# f30bms-slaveboard-tester.net
KiCad netlist of a schematic drawn in Altium Designer
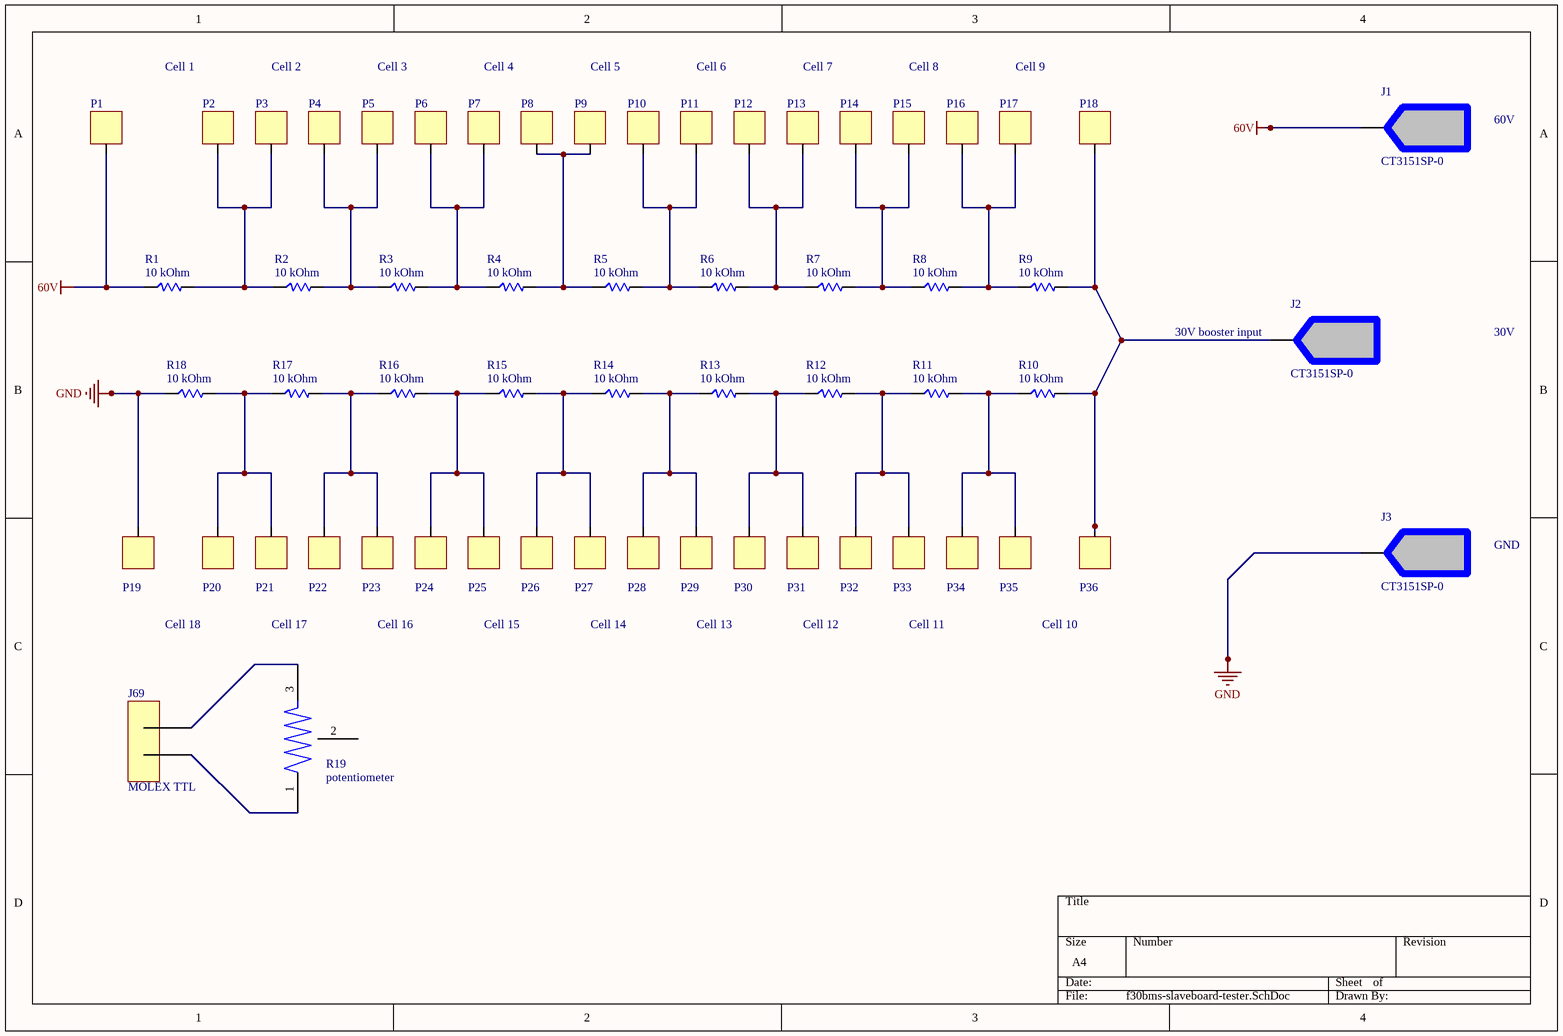
[diagram p0: f30bms-slaveboard-tester.SchDoc]

(export (version "E")
  (design (tool "Eeschema 10.0.6"))
  (components
    (comp (ref "J1")
      (value "CT3151SP-0")
      (footprint "CT3151SP-0")
      (description "Conn 4mm Safety Banana Jack F 1 POS Solder RA Thru-Hole 1 Port Bag")
      (fields (field (name "MANUFACTURER") "Cal Test Electronics"))
      (libsource (lib "connectors") (part "CT3151SP-0"))
    )
    (comp (ref "J2")
      (value "CT3151SP-0")
      (footprint "CT3151SP-0")
      (description "Conn 4mm Safety Banana Jack F 1 POS Solder RA Thru-Hole 1 Port Bag")
      (fields (field (name "MANUFACTURER") "Cal Test Electronics"))
      (libsource (lib "connectors") (part "CT3151SP-0"))
    )
    (comp (ref "J3")
      (value "CT3151SP-0")
      (footprint "CT3151SP-0")
      (description "Conn 4mm Safety Banana Jack F 1 POS Solder RA Thru-Hole 1 Port Bag")
      (fields (field (name "MANUFACTURER") "Cal Test Electronics"))
      (libsource (lib "connectors") (part "CT3151SP-0"))
    )
    (comp (ref "J69")
      (value "MOLEX TTL")
      (footprint "MOLEX TTL")
      (libsource (lib "connectors") (part "MOLEX TTL"))
    )
    (comp (ref "P1")
      (value "SLAVEBOARD CONTACT")
      (footprint "SLAVEBOARD CONTACT")
      (libsource (lib "connectors") (part "SLAVEBOARD CONTACT"))
    )
    (comp (ref "P2")
      (value "SLAVEBOARD CONTACT")
      (footprint "SLAVEBOARD CONTACT")
      (libsource (lib "connectors") (part "SLAVEBOARD CONTACT"))
    )
    (comp (ref "P3")
      (value "SLAVEBOARD CONTACT")
      (footprint "SLAVEBOARD CONTACT")
      (libsource (lib "connectors") (part "SLAVEBOARD CONTACT"))
    )
    (comp (ref "P4")
      (value "SLAVEBOARD CONTACT")
      (footprint "SLAVEBOARD CONTACT")
      (libsource (lib "connectors") (part "SLAVEBOARD CONTACT"))
    )
    (comp (ref "P5")
      (value "SLAVEBOARD CONTACT")
      (footprint "SLAVEBOARD CONTACT")
      (libsource (lib "connectors") (part "SLAVEBOARD CONTACT"))
    )
    (comp (ref "P6")
      (value "SLAVEBOARD CONTACT")
      (footprint "SLAVEBOARD CONTACT")
      (libsource (lib "connectors") (part "SLAVEBOARD CONTACT"))
    )
    (comp (ref "P7")
      (value "SLAVEBOARD CONTACT")
      (footprint "SLAVEBOARD CONTACT")
      (libsource (lib "connectors") (part "SLAVEBOARD CONTACT"))
    )
    (comp (ref "P8")
      (value "SLAVEBOARD CONTACT")
      (footprint "SLAVEBOARD CONTACT")
      (libsource (lib "connectors") (part "SLAVEBOARD CONTACT"))
    )
    (comp (ref "P9")
      (value "SLAVEBOARD CONTACT")
      (footprint "SLAVEBOARD CONTACT")
      (libsource (lib "connectors") (part "SLAVEBOARD CONTACT"))
    )
    (comp (ref "P10")
      (value "SLAVEBOARD CONTACT")
      (footprint "SLAVEBOARD CONTACT")
      (libsource (lib "connectors") (part "SLAVEBOARD CONTACT"))
    )
    (comp (ref "P11")
      (value "SLAVEBOARD CONTACT")
      (footprint "SLAVEBOARD CONTACT")
      (libsource (lib "connectors") (part "SLAVEBOARD CONTACT"))
    )
    (comp (ref "P12")
      (value "SLAVEBOARD CONTACT")
      (footprint "SLAVEBOARD CONTACT")
      (libsource (lib "connectors") (part "SLAVEBOARD CONTACT"))
    )
    (comp (ref "P13")
      (value "SLAVEBOARD CONTACT")
      (footprint "SLAVEBOARD CONTACT")
      (libsource (lib "connectors") (part "SLAVEBOARD CONTACT"))
    )
    (comp (ref "P14")
      (value "SLAVEBOARD CONTACT")
      (footprint "SLAVEBOARD CONTACT")
      (libsource (lib "connectors") (part "SLAVEBOARD CONTACT"))
    )
    (comp (ref "P15")
      (value "SLAVEBOARD CONTACT")
      (footprint "SLAVEBOARD CONTACT")
      (libsource (lib "connectors") (part "SLAVEBOARD CONTACT"))
    )
    (comp (ref "P16")
      (value "SLAVEBOARD CONTACT")
      (footprint "SLAVEBOARD CONTACT")
      (libsource (lib "connectors") (part "SLAVEBOARD CONTACT"))
    )
    (comp (ref "P17")
      (value "SLAVEBOARD CONTACT")
      (footprint "SLAVEBOARD CONTACT")
      (libsource (lib "connectors") (part "SLAVEBOARD CONTACT"))
    )
    (comp (ref "P18")
      (value "SLAVEBOARD CONTACT")
      (footprint "SLAVEBOARD CONTACT")
      (libsource (lib "connectors") (part "SLAVEBOARD CONTACT"))
    )
    (comp (ref "P19")
      (value "SLAVEBOARD CONTACT")
      (footprint "SLAVEBOARD CONTACT")
      (libsource (lib "") (part "SLAVEBOARD CONTACT_1"))
    )
    (comp (ref "P20")
      (value "SLAVEBOARD CONTACT")
      (footprint "SLAVEBOARD CONTACT")
      (libsource (lib "") (part "SLAVEBOARD CONTACT_1"))
    )
    (comp (ref "P21")
      (value "SLAVEBOARD CONTACT")
      (footprint "SLAVEBOARD CONTACT")
      (libsource (lib "") (part "SLAVEBOARD CONTACT_1"))
    )
    (comp (ref "P22")
      (value "SLAVEBOARD CONTACT")
      (footprint "SLAVEBOARD CONTACT")
      (libsource (lib "") (part "SLAVEBOARD CONTACT_1"))
    )
    (comp (ref "P23")
      (value "SLAVEBOARD CONTACT")
      (footprint "SLAVEBOARD CONTACT")
      (libsource (lib "") (part "SLAVEBOARD CONTACT_1"))
    )
    (comp (ref "P24")
      (value "SLAVEBOARD CONTACT")
      (footprint "SLAVEBOARD CONTACT")
      (libsource (lib "") (part "SLAVEBOARD CONTACT_1"))
    )
    (comp (ref "P25")
      (value "SLAVEBOARD CONTACT")
      (footprint "SLAVEBOARD CONTACT")
      (libsource (lib "") (part "SLAVEBOARD CONTACT_1"))
    )
    (comp (ref "P26")
      (value "SLAVEBOARD CONTACT")
      (footprint "SLAVEBOARD CONTACT")
      (libsource (lib "") (part "SLAVEBOARD CONTACT_1"))
    )
    (comp (ref "P27")
      (value "SLAVEBOARD CONTACT")
      (footprint "SLAVEBOARD CONTACT")
      (libsource (lib "") (part "SLAVEBOARD CONTACT_1"))
    )
    (comp (ref "P28")
      (value "SLAVEBOARD CONTACT")
      (footprint "SLAVEBOARD CONTACT")
      (libsource (lib "") (part "SLAVEBOARD CONTACT_1"))
    )
    (comp (ref "P29")
      (value "SLAVEBOARD CONTACT")
      (footprint "SLAVEBOARD CONTACT")
      (libsource (lib "") (part "SLAVEBOARD CONTACT_1"))
    )
    (comp (ref "P30")
      (value "SLAVEBOARD CONTACT")
      (footprint "SLAVEBOARD CONTACT")
      (libsource (lib "") (part "SLAVEBOARD CONTACT_1"))
    )
    (comp (ref "P31")
      (value "SLAVEBOARD CONTACT")
      (footprint "SLAVEBOARD CONTACT")
      (libsource (lib "") (part "SLAVEBOARD CONTACT_1"))
    )
    (comp (ref "P32")
      (value "SLAVEBOARD CONTACT")
      (footprint "SLAVEBOARD CONTACT")
      (libsource (lib "") (part "SLAVEBOARD CONTACT_1"))
    )
    (comp (ref "P33")
      (value "SLAVEBOARD CONTACT")
      (footprint "SLAVEBOARD CONTACT")
      (libsource (lib "") (part "SLAVEBOARD CONTACT_1"))
    )
    (comp (ref "P34")
      (value "SLAVEBOARD CONTACT")
      (footprint "SLAVEBOARD CONTACT")
      (libsource (lib "") (part "SLAVEBOARD CONTACT_1"))
    )
    (comp (ref "P35")
      (value "SLAVEBOARD CONTACT")
      (footprint "SLAVEBOARD CONTACT")
      (libsource (lib "") (part "SLAVEBOARD CONTACT_1"))
    )
    (comp (ref "P36")
      (value "SLAVEBOARD CONTACT")
      (footprint "SLAVEBOARD CONTACT")
      (libsource (lib "") (part "SLAVEBOARD CONTACT_1"))
    )
    (comp (ref "R1")
      (value "1622796-6")
      (footprint "CHP0805-FX-1002ELF - duplicate")
      (description "Res Thin Film 10K Ohm 0.1% 1/4W 15ppm/C Conformal AXL Thru-Hole Ammo Pack")
      (fields (field (name "MANUFACTURER") "TE Connectivity") (field (name "TOLERANCE") "0.1%"))
      (libsource (lib "resistors") (part "1622796-6"))
    )
    (comp (ref "R2")
      (value "1622796-6")
      (footprint "CHP0805-FX-1002ELF - duplicate")
      (description "Res Thin Film 10K Ohm 0.1% 1/4W 15ppm/C Conformal AXL Thru-Hole Ammo Pack")
      (fields (field (name "MANUFACTURER") "TE Connectivity") (field (name "TOLERANCE") "0.1%"))
      (libsource (lib "resistors") (part "1622796-6"))
    )
    (comp (ref "R3")
      (value "1622796-6")
      (footprint "CHP0805-FX-1002ELF - duplicate")
      (description "Res Thin Film 10K Ohm 0.1% 1/4W 15ppm/C Conformal AXL Thru-Hole Ammo Pack")
      (fields (field (name "MANUFACTURER") "TE Connectivity") (field (name "TOLERANCE") "0.1%"))
      (libsource (lib "resistors") (part "1622796-6"))
    )
    (comp (ref "R4")
      (value "1622796-6")
      (footprint "CHP0805-FX-1002ELF - duplicate")
      (description "Res Thin Film 10K Ohm 0.1% 1/4W 15ppm/C Conformal AXL Thru-Hole Ammo Pack")
      (fields (field (name "MANUFACTURER") "TE Connectivity") (field (name "TOLERANCE") "0.1%"))
      (libsource (lib "resistors") (part "1622796-6"))
    )
    (comp (ref "R5")
      (value "1622796-6")
      (footprint "CHP0805-FX-1002ELF - duplicate")
      (description "Res Thin Film 10K Ohm 0.1% 1/4W 15ppm/C Conformal AXL Thru-Hole Ammo Pack")
      (fields (field (name "MANUFACTURER") "TE Connectivity") (field (name "TOLERANCE") "0.1%"))
      (libsource (lib "resistors") (part "1622796-6"))
    )
    (comp (ref "R6")
      (value "1622796-6")
      (footprint "CHP0805-FX-1002ELF - duplicate")
      (description "Res Thin Film 10K Ohm 0.1% 1/4W 15ppm/C Conformal AXL Thru-Hole Ammo Pack")
      (fields (field (name "MANUFACTURER") "TE Connectivity") (field (name "TOLERANCE") "0.1%"))
      (libsource (lib "resistors") (part "1622796-6"))
    )
    (comp (ref "R7")
      (value "1622796-6")
      (footprint "CHP0805-FX-1002ELF - duplicate")
      (description "Res Thin Film 10K Ohm 0.1% 1/4W 15ppm/C Conformal AXL Thru-Hole Ammo Pack")
      (fields (field (name "MANUFACTURER") "TE Connectivity") (field (name "TOLERANCE") "0.1%"))
      (libsource (lib "resistors") (part "1622796-6"))
    )
    (comp (ref "R8")
      (value "1622796-6")
      (footprint "CHP0805-FX-1002ELF - duplicate")
      (description "Res Thin Film 10K Ohm 0.1% 1/4W 15ppm/C Conformal AXL Thru-Hole Ammo Pack")
      (fields (field (name "MANUFACTURER") "TE Connectivity") (field (name "TOLERANCE") "0.1%"))
      (libsource (lib "resistors") (part "1622796-6"))
    )
    (comp (ref "R9")
      (value "1622796-6")
      (footprint "CHP0805-FX-1002ELF - duplicate")
      (description "Res Thin Film 10K Ohm 0.1% 1/4W 15ppm/C Conformal AXL Thru-Hole Ammo Pack")
      (fields (field (name "MANUFACTURER") "TE Connectivity") (field (name "TOLERANCE") "0.1%"))
      (libsource (lib "resistors") (part "1622796-6"))
    )
    (comp (ref "R10")
      (value "1622796-6")
      (footprint "CHP0805-FX-1002ELF - duplicate")
      (description "Res Thin Film 10K Ohm 0.1% 1/4W 15ppm/C Conformal AXL Thru-Hole Ammo Pack")
      (fields (field (name "MANUFACTURER") "TE Connectivity") (field (name "TOLERANCE") "0.1%"))
      (libsource (lib "resistors") (part "1622796-6"))
    )
    (comp (ref "R11")
      (value "1622796-6")
      (footprint "CHP0805-FX-1002ELF - duplicate")
      (description "Res Thin Film 10K Ohm 0.1% 1/4W 15ppm/C Conformal AXL Thru-Hole Ammo Pack")
      (fields (field (name "MANUFACTURER") "TE Connectivity") (field (name "TOLERANCE") "0.1%"))
      (libsource (lib "resistors") (part "1622796-6"))
    )
    (comp (ref "R12")
      (value "1622796-6")
      (footprint "CHP0805-FX-1002ELF - duplicate")
      (description "Res Thin Film 10K Ohm 0.1% 1/4W 15ppm/C Conformal AXL Thru-Hole Ammo Pack")
      (fields (field (name "MANUFACTURER") "TE Connectivity") (field (name "TOLERANCE") "0.1%"))
      (libsource (lib "resistors") (part "1622796-6"))
    )
    (comp (ref "R13")
      (value "1622796-6")
      (footprint "CHP0805-FX-1002ELF - duplicate")
      (description "Res Thin Film 10K Ohm 0.1% 1/4W 15ppm/C Conformal AXL Thru-Hole Ammo Pack")
      (fields (field (name "MANUFACTURER") "TE Connectivity") (field (name "TOLERANCE") "0.1%"))
      (libsource (lib "resistors") (part "1622796-6"))
    )
    (comp (ref "R14")
      (value "1622796-6")
      (footprint "CHP0805-FX-1002ELF - duplicate")
      (description "Res Thin Film 10K Ohm 0.1% 1/4W 15ppm/C Conformal AXL Thru-Hole Ammo Pack")
      (fields (field (name "MANUFACTURER") "TE Connectivity") (field (name "TOLERANCE") "0.1%"))
      (libsource (lib "resistors") (part "1622796-6"))
    )
    (comp (ref "R15")
      (value "1622796-6")
      (footprint "CHP0805-FX-1002ELF - duplicate")
      (description "Res Thin Film 10K Ohm 0.1% 1/4W 15ppm/C Conformal AXL Thru-Hole Ammo Pack")
      (fields (field (name "MANUFACTURER") "TE Connectivity") (field (name "TOLERANCE") "0.1%"))
      (libsource (lib "resistors") (part "1622796-6"))
    )
    (comp (ref "R16")
      (value "1622796-6")
      (footprint "CHP0805-FX-1002ELF - duplicate")
      (description "Res Thin Film 10K Ohm 0.1% 1/4W 15ppm/C Conformal AXL Thru-Hole Ammo Pack")
      (fields (field (name "MANUFACTURER") "TE Connectivity") (field (name "TOLERANCE") "0.1%"))
      (libsource (lib "resistors") (part "1622796-6"))
    )
    (comp (ref "R17")
      (value "1622796-6")
      (footprint "CHP0805-FX-1002ELF - duplicate")
      (description "Res Thin Film 10K Ohm 0.1% 1/4W 15ppm/C Conformal AXL Thru-Hole Ammo Pack")
      (fields (field (name "MANUFACTURER") "TE Connectivity") (field (name "TOLERANCE") "0.1%"))
      (libsource (lib "resistors") (part "1622796-6"))
    )
    (comp (ref "R18")
      (value "1622796-6")
      (footprint "CHP0805-FX-1002ELF - duplicate")
      (description "Res Thin Film 10K Ohm 0.1% 1/4W 15ppm/C Conformal AXL Thru-Hole Ammo Pack")
      (fields (field (name "MANUFACTURER") "TE Connectivity") (field (name "TOLERANCE") "0.1%"))
      (libsource (lib "resistors") (part "1622796-6"))
    )
    (comp (ref "R19")
      (value "potentiometer")
      (footprint "3361P-1-103GLF_SOP3")
      (libsource (lib "resistors") (part "potentiometer"))
    )
  )
  (nets
    (net (code "1") (name "60V") (class "Default")
      (node (ref "J1") (pin "1") (pinfunction "1_1") (pintype "passive"))
      (node (ref "P1") (pin "1") (pinfunction "1_1") (pintype "passive"))
      (node (ref "R1") (pin "2") (pinfunction "2_2") (pintype "passive"))
    )
    (net (code "2") (name "GND") (class "Default")
      (node (ref "J3") (pin "1") (pinfunction "1_1") (pintype "passive"))
      (node (ref "P19") (pin "1") (pinfunction "1_1") (pintype "passive"))
      (node (ref "R18") (pin "2") (pinfunction "2_2") (pintype "passive"))
    )
    (net (code "3") (name "Net-(J2-Pad1)") (class "Default")
      (node (ref "J2") (pin "1") (pinfunction "1_1") (pintype "passive"))
      (node (ref "P18") (pin "1") (pinfunction "1_1") (pintype "passive"))
      (node (ref "P36") (pin "1") (pinfunction "1_1") (pintype "passive"))
      (node (ref "R10") (pin "1") (pinfunction "1_1") (pintype "passive"))
      (node (ref "R9") (pin "1") (pinfunction "1_1") (pintype "passive"))
    )
    (net (code "4") (name "Net-(J69-Pad1)") (class "Default")
      (node (ref "J69") (pin "1") (pinfunction "1_1") (pintype "passive"))
      (node (ref "R19") (pin "1") (pinfunction "1_1") (pintype "passive"))
    )
    (net (code "5") (name "Net-(J69-Pad2)") (class "Default")
      (node (ref "J69") (pin "2") (pinfunction "2_2") (pintype "passive"))
      (node (ref "R19") (pin "3") (pinfunction "3_3") (pintype "passive"))
    )
    (net (code "6") (name "Net-(P2-Pad1)") (class "Default")
      (node (ref "P2") (pin "1") (pinfunction "1_1") (pintype "passive"))
      (node (ref "P3") (pin "1") (pinfunction "1_1") (pintype "passive"))
      (node (ref "R1") (pin "1") (pinfunction "1_1") (pintype "passive"))
      (node (ref "R2") (pin "2") (pinfunction "2_2") (pintype "passive"))
    )
    (net (code "7") (name "Net-(P4-Pad1)") (class "Default")
      (node (ref "P4") (pin "1") (pinfunction "1_1") (pintype "passive"))
      (node (ref "P5") (pin "1") (pinfunction "1_1") (pintype "passive"))
      (node (ref "R2") (pin "1") (pinfunction "1_1") (pintype "passive"))
      (node (ref "R3") (pin "2") (pinfunction "2_2") (pintype "passive"))
    )
    (net (code "8") (name "Net-(P6-Pad1)") (class "Default")
      (node (ref "P6") (pin "1") (pinfunction "1_1") (pintype "passive"))
      (node (ref "P7") (pin "1") (pinfunction "1_1") (pintype "passive"))
      (node (ref "R3") (pin "1") (pinfunction "1_1") (pintype "passive"))
      (node (ref "R4") (pin "2") (pinfunction "2_2") (pintype "passive"))
    )
    (net (code "9") (name "Net-(P8-Pad1)") (class "Default")
      (node (ref "P8") (pin "1") (pinfunction "1_1") (pintype "passive"))
      (node (ref "P9") (pin "1") (pinfunction "1_1") (pintype "passive"))
      (node (ref "R4") (pin "1") (pinfunction "1_1") (pintype "passive"))
      (node (ref "R5") (pin "2") (pinfunction "2_2") (pintype "passive"))
    )
    (net (code "10") (name "Net-(P10-Pad1)") (class "Default")
      (node (ref "P10") (pin "1") (pinfunction "1_1") (pintype "passive"))
      (node (ref "P11") (pin "1") (pinfunction "1_1") (pintype "passive"))
      (node (ref "R5") (pin "1") (pinfunction "1_1") (pintype "passive"))
      (node (ref "R6") (pin "2") (pinfunction "2_2") (pintype "passive"))
    )
    (net (code "11") (name "Net-(P12-Pad1)") (class "Default")
      (node (ref "P12") (pin "1") (pinfunction "1_1") (pintype "passive"))
      (node (ref "P13") (pin "1") (pinfunction "1_1") (pintype "passive"))
      (node (ref "R6") (pin "1") (pinfunction "1_1") (pintype "passive"))
      (node (ref "R7") (pin "2") (pinfunction "2_2") (pintype "passive"))
    )
    (net (code "12") (name "Net-(P14-Pad1)") (class "Default")
      (node (ref "P14") (pin "1") (pinfunction "1_1") (pintype "passive"))
      (node (ref "P15") (pin "1") (pinfunction "1_1") (pintype "passive"))
      (node (ref "R7") (pin "1") (pinfunction "1_1") (pintype "passive"))
      (node (ref "R8") (pin "2") (pinfunction "2_2") (pintype "passive"))
    )
    (net (code "13") (name "Net-(P16-Pad1)") (class "Default")
      (node (ref "P16") (pin "1") (pinfunction "1_1") (pintype "passive"))
      (node (ref "P17") (pin "1") (pinfunction "1_1") (pintype "passive"))
      (node (ref "R8") (pin "1") (pinfunction "1_1") (pintype "passive"))
      (node (ref "R9") (pin "2") (pinfunction "2_2") (pintype "passive"))
    )
    (net (code "14") (name "Net-(P20-Pad1)") (class "Default")
      (node (ref "P20") (pin "1") (pinfunction "1_1") (pintype "passive"))
      (node (ref "P21") (pin "1") (pinfunction "1_1") (pintype "passive"))
      (node (ref "R17") (pin "2") (pinfunction "2_2") (pintype "passive"))
      (node (ref "R18") (pin "1") (pinfunction "1_1") (pintype "passive"))
    )
    (net (code "15") (name "Net-(P22-Pad1)") (class "Default")
      (node (ref "P22") (pin "1") (pinfunction "1_1") (pintype "passive"))
      (node (ref "P23") (pin "1") (pinfunction "1_1") (pintype "passive"))
      (node (ref "R16") (pin "2") (pinfunction "2_2") (pintype "passive"))
      (node (ref "R17") (pin "1") (pinfunction "1_1") (pintype "passive"))
    )
    (net (code "16") (name "Net-(P24-Pad1)") (class "Default")
      (node (ref "P24") (pin "1") (pinfunction "1_1") (pintype "passive"))
      (node (ref "P25") (pin "1") (pinfunction "1_1") (pintype "passive"))
      (node (ref "R15") (pin "2") (pinfunction "2_2") (pintype "passive"))
      (node (ref "R16") (pin "1") (pinfunction "1_1") (pintype "passive"))
    )
    (net (code "17") (name "Net-(P26-Pad1)") (class "Default")
      (node (ref "P26") (pin "1") (pinfunction "1_1") (pintype "passive"))
      (node (ref "P27") (pin "1") (pinfunction "1_1") (pintype "passive"))
      (node (ref "R14") (pin "2") (pinfunction "2_2") (pintype "passive"))
      (node (ref "R15") (pin "1") (pinfunction "1_1") (pintype "passive"))
    )
    (net (code "18") (name "Net-(P28-Pad1)") (class "Default")
      (node (ref "P28") (pin "1") (pinfunction "1_1") (pintype "passive"))
      (node (ref "P29") (pin "1") (pinfunction "1_1") (pintype "passive"))
      (node (ref "R13") (pin "2") (pinfunction "2_2") (pintype "passive"))
      (node (ref "R14") (pin "1") (pinfunction "1_1") (pintype "passive"))
    )
    (net (code "19") (name "Net-(P30-Pad1)") (class "Default")
      (node (ref "P30") (pin "1") (pinfunction "1_1") (pintype "passive"))
      (node (ref "P31") (pin "1") (pinfunction "1_1") (pintype "passive"))
      (node (ref "R12") (pin "2") (pinfunction "2_2") (pintype "passive"))
      (node (ref "R13") (pin "1") (pinfunction "1_1") (pintype "passive"))
    )
    (net (code "20") (name "Net-(P32-Pad1)") (class "Default")
      (node (ref "P32") (pin "1") (pinfunction "1_1") (pintype "passive"))
      (node (ref "P33") (pin "1") (pinfunction "1_1") (pintype "passive"))
      (node (ref "R11") (pin "2") (pinfunction "2_2") (pintype "passive"))
      (node (ref "R12") (pin "1") (pinfunction "1_1") (pintype "passive"))
    )
    (net (code "21") (name "Net-(P34-Pad1)") (class "Default")
      (node (ref "P34") (pin "1") (pinfunction "1_1") (pintype "passive"))
      (node (ref "P35") (pin "1") (pinfunction "1_1") (pintype "passive"))
      (node (ref "R10") (pin "2") (pinfunction "2_2") (pintype "passive"))
      (node (ref "R11") (pin "1") (pinfunction "1_1") (pintype "passive"))
    )
    (net (code "22") (name "unconnected-(R19-Pad2)") (class "Default")
      (node (ref "R19") (pin "2") (pinfunction "2_2") (pintype "passive"))
    )
  )
)
